# PJ24.net
KiCad netlist of a schematic drawn in EAGLE
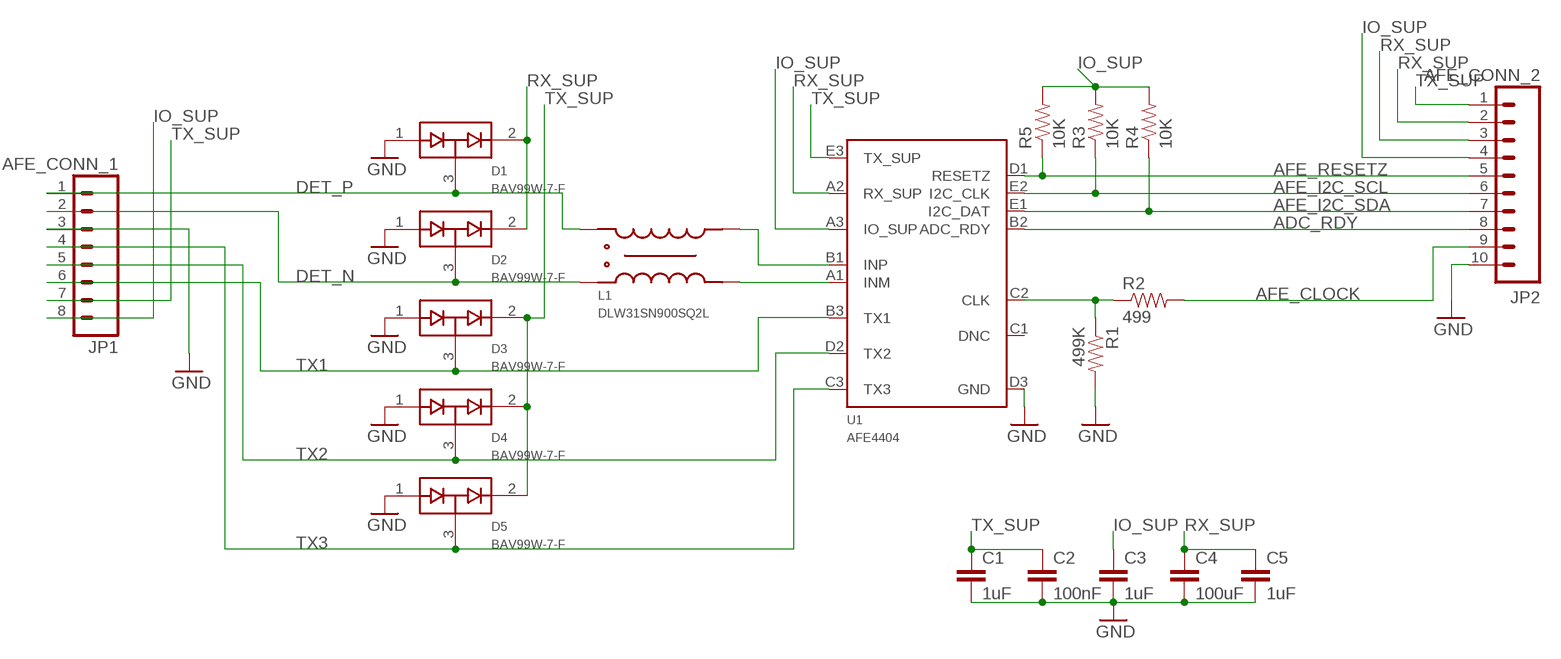
[diagram p0: schematic, sheet 1]
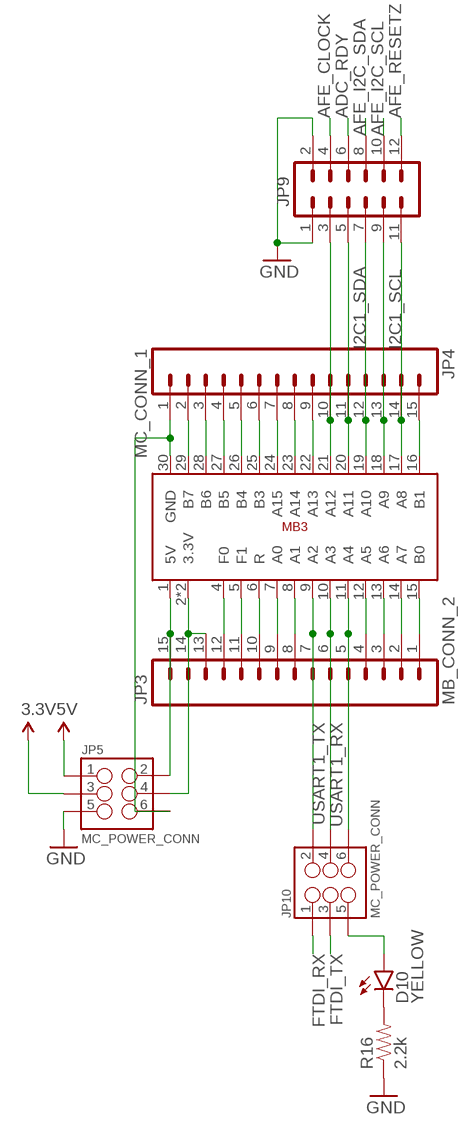
[diagram p1: schematic, sheet 2]
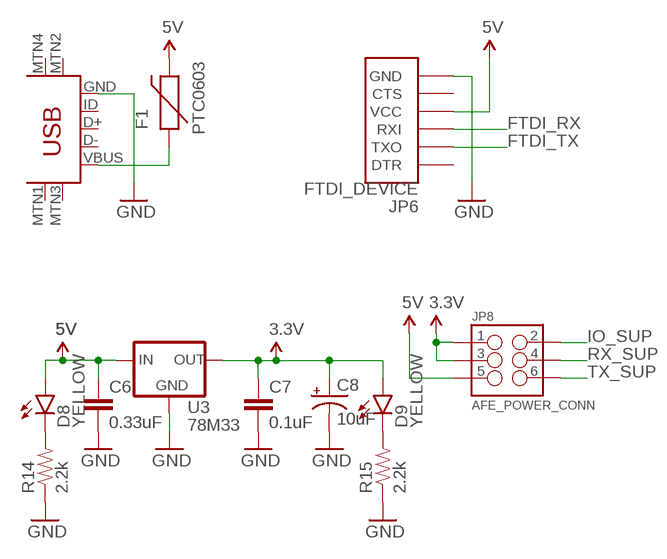
[diagram p2: schematic, sheet 3]
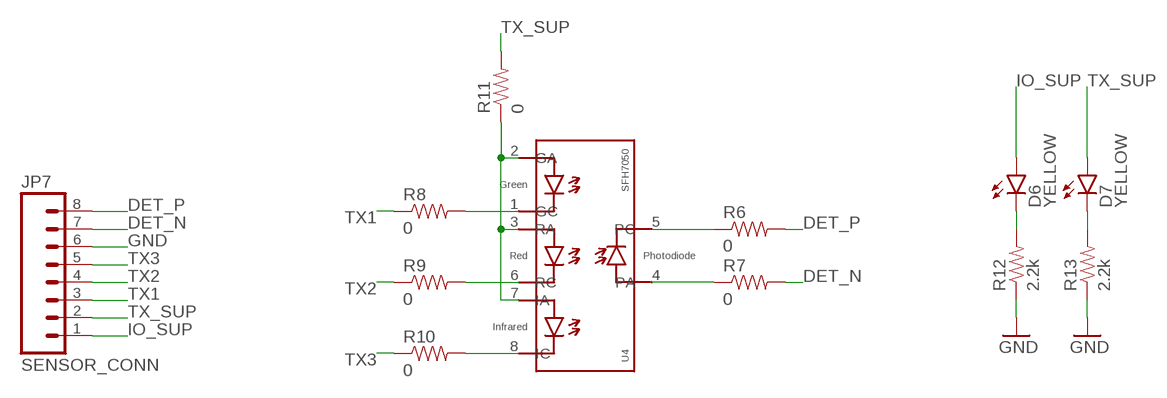
[diagram p3: schematic, sheet 4]

(export (version "E")
  (design (tool "Eeschema 10.0.6"))
  (components
    (comp (ref "D6")
      (value "YELLOW")
      (footprint "eagle-import:LED-1206")
      (libsource (lib "eagle-import") (part "LED-YELLOW1206"))
    )
    (comp (ref "D7")
      (value "YELLOW")
      (footprint "eagle-import:LED-1206")
      (libsource (lib "eagle-import") (part "LED-YELLOW1206"))
    )
    (comp (ref "JP7")
      (value "SENSOR_CONN")
      (footprint "eagle-import:BM08B-SRSS-TB")
      (libsource (lib "eagle-import") (part "M08BM08B-SRSS-TB"))
    )
    (comp (ref "R6")
      (value "0")
      (footprint "eagle-import:0402-S")
      (libsource (lib "eagle-import") (part "RESISTOR0402-S"))
    )
    (comp (ref "R7")
      (value "0")
      (footprint "eagle-import:0402-S")
      (libsource (lib "eagle-import") (part "RESISTOR0402-S"))
    )
    (comp (ref "R8")
      (value "0")
      (footprint "eagle-import:0402-S")
      (libsource (lib "eagle-import") (part "RESISTOR0402-S"))
    )
    (comp (ref "R9")
      (value "0")
      (footprint "eagle-import:0402-S")
      (libsource (lib "eagle-import") (part "RESISTOR0402-S"))
    )
    (comp (ref "R10")
      (value "0")
      (footprint "eagle-import:0402-S")
      (libsource (lib "eagle-import") (part "RESISTOR0402-S"))
    )
    (comp (ref "R11")
      (value "0")
      (footprint "eagle-import:0402-S")
      (libsource (lib "eagle-import") (part "RESISTOR0402-S"))
    )
    (comp (ref "R12")
      (value "2.2k")
      (footprint "eagle-import:0603-RES")
      (libsource (lib "eagle-import") (part "2.2KOHM-1/10W-1%(0603)"))
    )
    (comp (ref "R13")
      (value "2.2k")
      (footprint "eagle-import:0603-RES")
      (libsource (lib "eagle-import") (part "2.2KOHM-1/10W-1%(0603)"))
    )
    (comp (ref "U4")
      (value "SFH7050")
      (footprint "eagle-import:SFH7050")
      (libsource (lib "eagle-import") (part "SFH7050"))
    )
    (comp (ref "C1")
      (value "1uF")
      (footprint "eagle-import:0402-S")
      (libsource (lib "eagle-import") (part "CAP0402-S"))
    )
    (comp (ref "C2")
      (value "100nF")
      (footprint "eagle-import:0402-S")
      (libsource (lib "eagle-import") (part "CAP0402-S"))
    )
    (comp (ref "C3")
      (value "1uF")
      (footprint "eagle-import:0402-S")
      (libsource (lib "eagle-import") (part "CAP0402-S"))
    )
    (comp (ref "C4")
      (value "100uF")
      (footprint "eagle-import:0402-S")
      (libsource (lib "eagle-import") (part "CAP0402-S"))
    )
    (comp (ref "C5")
      (value "1uF")
      (footprint "eagle-import:0402-S")
      (libsource (lib "eagle-import") (part "CAP0402-S"))
    )
    (comp (ref "D1")
      (value "BAV99W-7-F")
      (footprint "eagle-import:SOT323")
      (libsource (lib "eagle-import") (part "BAV99W"))
    )
    (comp (ref "D2")
      (value "BAV99W-7-F")
      (footprint "eagle-import:SOT323")
      (libsource (lib "eagle-import") (part "BAV99W"))
    )
    (comp (ref "D3")
      (value "BAV99W-7-F")
      (footprint "eagle-import:SOT323")
      (libsource (lib "eagle-import") (part "BAV99W"))
    )
    (comp (ref "D4")
      (value "BAV99W-7-F")
      (footprint "eagle-import:SOT323")
      (libsource (lib "eagle-import") (part "BAV99W"))
    )
    (comp (ref "D5")
      (value "BAV99W-7-F")
      (footprint "eagle-import:SOT323")
      (libsource (lib "eagle-import") (part "BAV99W"))
    )
    (comp (ref "JP1")
      (value "AFE_CONN_1")
      (footprint "eagle-import:BM08B-SRSS-TB")
      (libsource (lib "eagle-import") (part "M08BM08B-SRSS-TB"))
    )
    (comp (ref "JP2")
      (value "AFE_CONN_2")
      (footprint "eagle-import:1X10_SMD_MALE")
      (libsource (lib "eagle-import") (part "M10SMD_MALE"))
    )
    (comp (ref "L1")
      (value "DLW31SN900SQ2L")
      (footprint "eagle-import:DLW31SN900SQ2L")
      (libsource (lib "eagle-import") (part "DLW31SN900SQ2L"))
    )
    (comp (ref "R1")
      (value "499K")
      (footprint "eagle-import:0402-S")
      (libsource (lib "eagle-import") (part "RESISTOR0402-S"))
    )
    (comp (ref "R2")
      (value "499")
      (footprint "eagle-import:0402-S")
      (libsource (lib "eagle-import") (part "RESISTOR0402-S"))
    )
    (comp (ref "R3")
      (value "10K")
      (footprint "eagle-import:0402-S")
      (libsource (lib "eagle-import") (part "RESISTOR0402-S"))
    )
    (comp (ref "R4")
      (value "10K")
      (footprint "eagle-import:0402-S")
      (libsource (lib "eagle-import") (part "RESISTOR0402-S"))
    )
    (comp (ref "R5")
      (value "10K")
      (footprint "eagle-import:0402-S")
      (libsource (lib "eagle-import") (part "RESISTOR0402-S"))
    )
    (comp (ref "U1")
      (value "AFE4404")
      (footprint "eagle-import:DSBGA-3X5")
      (libsource (lib "eagle-import") (part "AFE4404"))
    )
    (comp (ref "C6")
      (value "0.33uF")
      (footprint "eagle-import:0805-CAP")
      (libsource (lib "eagle-import") (part "0.33UF-50V-10%(0805)"))
    )
    (comp (ref "C7")
      (value "0.1uF")
      (footprint "eagle-import:0805-CAP")
      (libsource (lib "eagle-import") (part "0.33UF-50V-10%(0805)"))
    )
    (comp (ref "C8")
      (value "10uF")
      (footprint "eagle-import:EIA3216")
      (libsource (lib "eagle-import") (part "10UF-16V-10%(TANT)"))
    )
    (comp (ref "D8")
      (value "YELLOW")
      (footprint "eagle-import:LED-1206")
      (libsource (lib "eagle-import") (part "LED-YELLOW1206"))
    )
    (comp (ref "D9")
      (value "YELLOW")
      (footprint "eagle-import:LED-1206")
      (libsource (lib "eagle-import") (part "LED-YELLOW1206"))
    )
    (comp (ref "F1")
      (value "PTC0603")
      (footprint "eagle-import:0603")
      (libsource (lib "eagle-import") (part "PTC0603"))
    )
    (comp (ref "JP6")
      (value "FTDI_DEVICE")
      (footprint "eagle-import:FTDI_DEVICE_SIDE")
      (libsource (lib "eagle-import") (part "FTDI_DEVICE"))
    )
    (comp (ref "JP8")
      (value "AFE_POWER_CONN")
      (footprint "eagle-import:2X3_SMT_POSTS")
      (libsource (lib "eagle-import") (part "M03X2SMT"))
    )
    (comp (ref "R14")
      (value "2.2k")
      (footprint "eagle-import:0603-RES")
      (libsource (lib "eagle-import") (part "2.2KOHM-1/10W-1%(0603)"))
    )
    (comp (ref "R15")
      (value "2.2k")
      (footprint "eagle-import:0603-RES")
      (libsource (lib "eagle-import") (part "2.2KOHM-1/10W-1%(0603)"))
    )
    (comp (ref "U$1")
      (value "USB-MINIB-5PIN")
      (footprint "eagle-import:USB-MINIB")
      (libsource (lib "eagle-import") (part "USB-MINIB-5PIN"))
    )
    (comp (ref "U3")
      (value "78M33")
      (footprint "eagle-import:TO-252")
      (libsource (lib "eagle-import") (part "V_REG_78XX7812"))
    )
    (comp (ref "D10")
      (value "YELLOW")
      (footprint "eagle-import:LED-1206")
      (libsource (lib "eagle-import") (part "LED-YELLOW1206"))
    )
    (comp (ref "JP3")
      (value "MB_CONN_2")
      (footprint "eagle-import:1X15_LOCK")
      (libsource (lib "eagle-import") (part "M15LOCK"))
    )
    (comp (ref "JP4")
      (value "MC_CONN_1")
      (footprint "eagle-import:1X15_LOCK")
      (libsource (lib "eagle-import") (part "M15LOCK"))
    )
    (comp (ref "JP5")
      (value "MC_POWER_CONN")
      (footprint "eagle-import:2X3_SMT_POSTS")
      (libsource (lib "eagle-import") (part "M03X2SMT"))
    )
    (comp (ref "JP9")
      (value "M06X2FEMALE-SMT")
      (footprint "eagle-import:2X6_SMD")
      (libsource (lib "eagle-import") (part "M06X2FEMALE-SMT"))
    )
    (comp (ref "JP10")
      (value "MC_POWER_CONN")
      (footprint "eagle-import:2X3_SMT_POSTS")
      (libsource (lib "eagle-import") (part "M03X2SMT"))
    )
    (comp (ref "R16")
      (value "2.2k")
      (footprint "eagle-import:0603-RES")
      (libsource (lib "eagle-import") (part "2.2KOHM-1/10W-1%(0603)"))
    )
    (comp (ref "U2")
      (value "MB3")
      (footprint "eagle-import:MB3")
      (libsource (lib "eagle-import") (part "MB3"))
    )
  )
  (nets
    (net (code "1") (name "3.3V") (class "Default")
      (node (ref "C7") (pin "1") (pinfunction "1_1") (pintype "passive"))
      (node (ref "C8") (pin "A") (pinfunction "+_A") (pintype "passive"))
      (node (ref "D9") (pin "A") (pinfunction "A_A") (pintype "passive"))
      (node (ref "JP5") (pin "3") (pinfunction "3_3") (pintype "bidirectional"))
      (node (ref "JP8") (pin "1") (pinfunction "1_1") (pintype "bidirectional"))
      (node (ref "JP8") (pin "3") (pinfunction "3_3") (pintype "bidirectional"))
      (node (ref "U3") (pin "2") (pinfunction "OUT_2") (pintype "passive"))
    )
    (net (code "2") (name "5V") (class "Default")
      (node (ref "C6") (pin "1") (pinfunction "1_1") (pintype "passive"))
      (node (ref "D8") (pin "A") (pinfunction "A_A") (pintype "passive"))
      (node (ref "F1") (pin "2") (pinfunction "2_2") (pintype "bidirectional"))
      (node (ref "JP5") (pin "1") (pinfunction "1_1") (pintype "bidirectional"))
      (node (ref "JP6") (pin "P$4") (pinfunction "VCC_P$4") (pintype "bidirectional"))
      (node (ref "JP8") (pin "5") (pinfunction "5_5") (pintype "bidirectional"))
      (node (ref "U3") (pin "1") (pinfunction "IN_1") (pintype "input"))
    )
    (net (code "3") (name "ADC_RDY") (class "Default")
      (node (ref "JP2") (pin "8") (pinfunction "8_8") (pintype "passive"))
      (node (ref "JP9") (pin "6") (pinfunction "6_6") (pintype "passive"))
      (node (ref "U1") (pin "B2") (pinfunction "ADC_RDY_B2") (pintype "bidirectional"))
    )
    (net (code "4") (name "AFE_CLOCK") (class "Default")
      (node (ref "JP2") (pin "9") (pinfunction "9_9") (pintype "passive"))
      (node (ref "JP9") (pin "4") (pinfunction "4_4") (pintype "passive"))
      (node (ref "R2") (pin "2") (pinfunction "2_2") (pintype "passive"))
    )
    (net (code "5") (name "AFE_I2C_SCL") (class "Default")
      (node (ref "JP2") (pin "6") (pinfunction "6_6") (pintype "passive"))
      (node (ref "JP9") (pin "10") (pinfunction "10_10") (pintype "passive"))
      (node (ref "R3") (pin "1") (pinfunction "1_1") (pintype "passive"))
      (node (ref "U1") (pin "E2") (pinfunction "I2C_CLK_E2") (pintype "bidirectional"))
    )
    (net (code "6") (name "AFE_I2C_SDA") (class "Default")
      (node (ref "JP2") (pin "7") (pinfunction "7_7") (pintype "passive"))
      (node (ref "JP9") (pin "8") (pinfunction "8_8") (pintype "passive"))
      (node (ref "R4") (pin "1") (pinfunction "1_1") (pintype "passive"))
      (node (ref "U1") (pin "E1") (pinfunction "I2C_DAT_E1") (pintype "bidirectional"))
    )
    (net (code "7") (name "AFE_RESETZ") (class "Default")
      (node (ref "JP2") (pin "5") (pinfunction "5_5") (pintype "passive"))
      (node (ref "JP9") (pin "12") (pinfunction "12_12") (pintype "passive"))
      (node (ref "R5") (pin "1") (pinfunction "1_1") (pintype "passive"))
      (node (ref "U1") (pin "D1") (pinfunction "RESETZ_D1") (pintype "bidirectional"))
    )
    (net (code "8") (name "DET_N") (class "Default")
      (node (ref "D2") (pin "3") (pinfunction "COM_3") (pintype "bidirectional"))
      (node (ref "JP1") (pin "2") (pinfunction "2_2") (pintype "passive"))
      (node (ref "JP7") (pin "7") (pinfunction "7_7") (pintype "passive"))
      (node (ref "L1") (pin "4") (pinfunction "4_4") (pintype "bidirectional"))
      (node (ref "R7") (pin "2") (pinfunction "2_2") (pintype "passive"))
    )
    (net (code "9") (name "DET_P") (class "Default")
      (node (ref "D1") (pin "3") (pinfunction "COM_3") (pintype "bidirectional"))
      (node (ref "JP1") (pin "1") (pinfunction "1_1") (pintype "passive"))
      (node (ref "JP7") (pin "8") (pinfunction "8_8") (pintype "passive"))
      (node (ref "L1") (pin "1") (pinfunction "1_1") (pintype "bidirectional"))
      (node (ref "R6") (pin "2") (pinfunction "2_2") (pintype "passive"))
    )
    (net (code "10") (name "FTDI_RX") (class "Default")
      (node (ref "JP10") (pin "1") (pinfunction "1_1") (pintype "bidirectional"))
      (node (ref "JP6") (pin "P$3") (pinfunction "RXI_P$3") (pintype "bidirectional"))
    )
    (net (code "11") (name "FTDI_TX") (class "Default")
      (node (ref "JP10") (pin "3") (pinfunction "3_3") (pintype "bidirectional"))
      (node (ref "JP6") (pin "P$2") (pinfunction "TXO_P$2") (pintype "bidirectional"))
    )
    (net (code "12") (name "GND") (class "Default")
      (node (ref "C1") (pin "2") (pinfunction "2_2") (pintype "passive"))
      (node (ref "C2") (pin "2") (pinfunction "2_2") (pintype "passive"))
      (node (ref "C3") (pin "2") (pinfunction "2_2") (pintype "passive"))
      (node (ref "C4") (pin "2") (pinfunction "2_2") (pintype "passive"))
      (node (ref "C5") (pin "2") (pinfunction "2_2") (pintype "passive"))
      (node (ref "C6") (pin "2") (pinfunction "2_2") (pintype "passive"))
      (node (ref "C7") (pin "2") (pinfunction "2_2") (pintype "passive"))
      (node (ref "C8") (pin "C") (pinfunction "-_C") (pintype "passive"))
      (node (ref "D1") (pin "1") (pinfunction "A1_1") (pintype "bidirectional"))
      (node (ref "D2") (pin "1") (pinfunction "A1_1") (pintype "bidirectional"))
      (node (ref "D3") (pin "1") (pinfunction "A1_1") (pintype "bidirectional"))
      (node (ref "D4") (pin "1") (pinfunction "A1_1") (pintype "bidirectional"))
      (node (ref "D5") (pin "1") (pinfunction "A1_1") (pintype "bidirectional"))
      (node (ref "JP1") (pin "3") (pinfunction "3_3") (pintype "passive"))
      (node (ref "JP2") (pin "10") (pinfunction "10_10") (pintype "passive"))
      (node (ref "JP5") (pin "5") (pinfunction "5_5") (pintype "bidirectional"))
      (node (ref "JP6") (pin "P$6") (pinfunction "GND_P$6") (pintype "bidirectional"))
      (node (ref "JP7") (pin "6") (pinfunction "6_6") (pintype "passive"))
      (node (ref "JP9") (pin "1") (pinfunction "1_1") (pintype "passive"))
      (node (ref "JP9") (pin "2") (pinfunction "2_2") (pintype "passive"))
      (node (ref "R1") (pin "2") (pinfunction "2_2") (pintype "passive"))
      (node (ref "R12") (pin "1") (pinfunction "1_1") (pintype "passive"))
      (node (ref "R13") (pin "1") (pinfunction "1_1") (pintype "passive"))
      (node (ref "R14") (pin "1") (pinfunction "1_1") (pintype "passive"))
      (node (ref "R15") (pin "1") (pinfunction "1_1") (pintype "passive"))
      (node (ref "R16") (pin "1") (pinfunction "1_1") (pintype "passive"))
      (node (ref "U$1") (pin "GND") (pinfunction "GND_GND") (pintype "bidirectional"))
      (node (ref "U1") (pin "D3") (pinfunction "GND_D3") (pintype "bidirectional"))
      (node (ref "U3") (pin "3") (pinfunction "GND_3") (pintype "input"))
    )
    (net (code "13") (name "I2C1_SCL") (class "Default")
      (node (ref "JP4") (pin "13") (pinfunction "13_13") (pintype "passive"))
      (node (ref "JP9") (pin "9") (pinfunction "9_9") (pintype "passive"))
      (node (ref "U2") (pin "18") (pinfunction "A9_18") (pintype "bidirectional"))
    )
    (net (code "14") (name "I2C1_SDA") (class "Default")
      (node (ref "JP4") (pin "12") (pinfunction "12_12") (pintype "passive"))
      (node (ref "JP9") (pin "7") (pinfunction "7_7") (pintype "passive"))
      (node (ref "U2") (pin "19") (pinfunction "A10_19") (pintype "bidirectional"))
    )
    (net (code "15") (name "IO_SUP") (class "Default")
      (node (ref "C3") (pin "1") (pinfunction "1_1") (pintype "passive"))
      (node (ref "D6") (pin "A") (pinfunction "A_A") (pintype "passive"))
      (node (ref "JP1") (pin "8") (pinfunction "8_8") (pintype "passive"))
      (node (ref "JP2") (pin "4") (pinfunction "4_4") (pintype "passive"))
      (node (ref "JP7") (pin "1") (pinfunction "1_1") (pintype "passive"))
      (node (ref "JP8") (pin "2") (pinfunction "2_2") (pintype "bidirectional"))
      (node (ref "R3") (pin "2") (pinfunction "2_2") (pintype "passive"))
      (node (ref "R4") (pin "2") (pinfunction "2_2") (pintype "passive"))
      (node (ref "R5") (pin "2") (pinfunction "2_2") (pintype "passive"))
      (node (ref "U1") (pin "A3") (pinfunction "IO_SUP_A3") (pintype "bidirectional"))
    )
    (net (code "16") (name "Net-(D6-PadC)") (class "Default")
      (node (ref "D6") (pin "C") (pinfunction "C_C") (pintype "passive"))
      (node (ref "R12") (pin "2") (pinfunction "2_2") (pintype "passive"))
    )
    (net (code "17") (name "Net-(D7-PadC)") (class "Default")
      (node (ref "D7") (pin "C") (pinfunction "C_C") (pintype "passive"))
      (node (ref "R13") (pin "2") (pinfunction "2_2") (pintype "passive"))
    )
    (net (code "18") (name "Net-(D8-PadC)") (class "Default")
      (node (ref "D8") (pin "C") (pinfunction "C_C") (pintype "passive"))
      (node (ref "R14") (pin "2") (pinfunction "2_2") (pintype "passive"))
    )
    (net (code "19") (name "Net-(D9-PadC)") (class "Default")
      (node (ref "D9") (pin "C") (pinfunction "C_C") (pintype "passive"))
      (node (ref "R15") (pin "2") (pinfunction "2_2") (pintype "passive"))
    )
    (net (code "20") (name "Net-(D10-PadA)") (class "Default")
      (node (ref "D10") (pin "A") (pinfunction "A_A") (pintype "passive"))
      (node (ref "JP10") (pin "5") (pinfunction "5_5") (pintype "bidirectional"))
    )
    (net (code "21") (name "Net-(D10-PadC)") (class "Default")
      (node (ref "D10") (pin "C") (pinfunction "C_C") (pintype "passive"))
      (node (ref "R16") (pin "2") (pinfunction "2_2") (pintype "passive"))
    )
    (net (code "22") (name "Net-(F1-Pad1)") (class "Default")
      (node (ref "F1") (pin "1") (pinfunction "1_1") (pintype "bidirectional"))
      (node (ref "U$1") (pin "VBUS") (pinfunction "VBUS_VBUS") (pintype "bidirectional"))
    )
    (net (code "23") (name "Net-(JP3-Pad13)") (class "Default")
      (node (ref "JP3") (pin "13") (pinfunction "13_13") (pintype "passive"))
      (node (ref "JP3") (pin "14") (pinfunction "14_14") (pintype "passive"))
      (node (ref "JP5") (pin "4") (pinfunction "4_4") (pintype "bidirectional"))
      (node (ref "U2") (pin "2") (pinfunction "3.3V_2") (pintype "bidirectional"))
      (node (ref "U2") (pin "3") (pinfunction "3.3V_3") (pintype "bidirectional"))
    )
    (net (code "24") (name "Net-(U1-CLK)") (class "Default")
      (node (ref "R1") (pin "1") (pinfunction "1_1") (pintype "passive"))
      (node (ref "R2") (pin "1") (pinfunction "1_1") (pintype "passive"))
      (node (ref "U1") (pin "C2") (pinfunction "CLK_C2") (pintype "bidirectional"))
    )
    (net (code "25") (name "Net-(U1-INM)") (class "Default")
      (node (ref "L1") (pin "3") (pinfunction "3_3") (pintype "bidirectional"))
      (node (ref "U1") (pin "A1") (pinfunction "INM_A1") (pintype "bidirectional"))
    )
    (net (code "26") (name "Net-(U1-INP)") (class "Default")
      (node (ref "L1") (pin "2") (pinfunction "2_2") (pintype "bidirectional"))
      (node (ref "U1") (pin "B1") (pinfunction "INP_B1") (pintype "bidirectional"))
    )
    (net (code "27") (name "Net-(U2-5V)") (class "Default")
      (node (ref "JP3") (pin "15") (pinfunction "15_15") (pintype "passive"))
      (node (ref "JP5") (pin "2") (pinfunction "2_2") (pintype "bidirectional"))
      (node (ref "U2") (pin "1") (pinfunction "5V_1") (pintype "bidirectional"))
    )
    (net (code "28") (name "Net-(U2-A0)") (class "Default")
      (node (ref "JP3") (pin "9") (pinfunction "9_9") (pintype "passive"))
      (node (ref "U2") (pin "7") (pinfunction "A0_7") (pintype "bidirectional"))
    )
    (net (code "29") (name "Net-(U2-A1)") (class "Default")
      (node (ref "JP3") (pin "8") (pinfunction "8_8") (pintype "passive"))
      (node (ref "U2") (pin "8") (pinfunction "A1_8") (pintype "bidirectional"))
    )
    (net (code "30") (name "Net-(U2-A4)") (class "Default")
      (node (ref "JP10") (pin "6") (pinfunction "6_6") (pintype "bidirectional"))
      (node (ref "JP3") (pin "5") (pinfunction "5_5") (pintype "passive"))
      (node (ref "U2") (pin "11") (pinfunction "A4_11") (pintype "bidirectional"))
    )
    (net (code "31") (name "Net-(U2-A5)") (class "Default")
      (node (ref "JP3") (pin "4") (pinfunction "4_4") (pintype "passive"))
      (node (ref "U2") (pin "12") (pinfunction "A5_12") (pintype "bidirectional"))
    )
    (net (code "32") (name "Net-(U2-A6)") (class "Default")
      (node (ref "JP3") (pin "3") (pinfunction "3_3") (pintype "passive"))
      (node (ref "U2") (pin "13") (pinfunction "A6_13") (pintype "bidirectional"))
    )
    (net (code "33") (name "Net-(U2-A7)") (class "Default")
      (node (ref "JP3") (pin "2") (pinfunction "2_2") (pintype "passive"))
      (node (ref "U2") (pin "14") (pinfunction "A7_14") (pintype "bidirectional"))
    )
    (net (code "34") (name "Net-(U2-A8)") (class "Default")
      (node (ref "JP4") (pin "14") (pinfunction "14_14") (pintype "passive"))
      (node (ref "JP9") (pin "11") (pinfunction "11_11") (pintype "passive"))
      (node (ref "U2") (pin "17") (pinfunction "A8_17") (pintype "bidirectional"))
    )
    (net (code "35") (name "Net-(U2-A11)") (class "Default")
      (node (ref "JP4") (pin "11") (pinfunction "11_11") (pintype "passive"))
      (node (ref "JP9") (pin "5") (pinfunction "5_5") (pintype "passive"))
      (node (ref "U2") (pin "20") (pinfunction "A11_20") (pintype "bidirectional"))
    )
    (net (code "36") (name "Net-(U2-A12)") (class "Default")
      (node (ref "JP4") (pin "10") (pinfunction "10_10") (pintype "passive"))
      (node (ref "JP9") (pin "3") (pinfunction "3_3") (pintype "passive"))
      (node (ref "U2") (pin "21") (pinfunction "A12_21") (pintype "bidirectional"))
    )
    (net (code "37") (name "Net-(U2-A13)") (class "Default")
      (node (ref "JP4") (pin "9") (pinfunction "9_9") (pintype "passive"))
      (node (ref "U2") (pin "22") (pinfunction "A13_22") (pintype "bidirectional"))
    )
    (net (code "38") (name "Net-(U2-A14)") (class "Default")
      (node (ref "JP4") (pin "8") (pinfunction "8_8") (pintype "passive"))
      (node (ref "U2") (pin "23") (pinfunction "A14_23") (pintype "bidirectional"))
    )
    (net (code "39") (name "Net-(U2-A15)") (class "Default")
      (node (ref "JP4") (pin "7") (pinfunction "7_7") (pintype "passive"))
      (node (ref "U2") (pin "24") (pinfunction "A15_24") (pintype "bidirectional"))
    )
    (net (code "40") (name "Net-(U2-B0)") (class "Default")
      (node (ref "JP3") (pin "1") (pinfunction "1_1") (pintype "passive"))
      (node (ref "U2") (pin "15") (pinfunction "B0_15") (pintype "bidirectional"))
    )
    (net (code "41") (name "Net-(U2-B1)") (class "Default")
      (node (ref "JP4") (pin "15") (pinfunction "15_15") (pintype "passive"))
      (node (ref "U2") (pin "16") (pinfunction "B1_16") (pintype "bidirectional"))
    )
    (net (code "42") (name "Net-(U2-B3)") (class "Default")
      (node (ref "JP4") (pin "6") (pinfunction "6_6") (pintype "passive"))
      (node (ref "U2") (pin "25") (pinfunction "B3_25") (pintype "bidirectional"))
    )
    (net (code "43") (name "Net-(U2-B4)") (class "Default")
      (node (ref "JP4") (pin "5") (pinfunction "5_5") (pintype "passive"))
      (node (ref "U2") (pin "26") (pinfunction "B4_26") (pintype "bidirectional"))
    )
    (net (code "44") (name "Net-(U2-B5)") (class "Default")
      (node (ref "JP4") (pin "4") (pinfunction "4_4") (pintype "passive"))
      (node (ref "U2") (pin "27") (pinfunction "B5_27") (pintype "bidirectional"))
    )
    (net (code "45") (name "Net-(U2-B6)") (class "Default")
      (node (ref "JP4") (pin "3") (pinfunction "3_3") (pintype "passive"))
      (node (ref "U2") (pin "28") (pinfunction "B6_28") (pintype "bidirectional"))
    )
    (net (code "46") (name "Net-(U2-B7)") (class "Default")
      (node (ref "JP4") (pin "2") (pinfunction "2_2") (pintype "passive"))
      (node (ref "U2") (pin "29") (pinfunction "B7_29") (pintype "bidirectional"))
    )
    (net (code "47") (name "Net-(U2-F0)") (class "Default")
      (node (ref "JP3") (pin "12") (pinfunction "12_12") (pintype "passive"))
      (node (ref "U2") (pin "4") (pinfunction "F0_4") (pintype "bidirectional"))
    )
    (net (code "48") (name "Net-(U2-F1)") (class "Default")
      (node (ref "JP3") (pin "11") (pinfunction "11_11") (pintype "passive"))
      (node (ref "U2") (pin "5") (pinfunction "F1_5") (pintype "bidirectional"))
    )
    (net (code "49") (name "Net-(U2-GND)") (class "Default")
      (node (ref "JP4") (pin "1") (pinfunction "1_1") (pintype "passive"))
      (node (ref "JP5") (pin "6") (pinfunction "6_6") (pintype "bidirectional"))
      (node (ref "U2") (pin "30") (pinfunction "GND_30") (pintype "bidirectional"))
    )
    (net (code "50") (name "Net-(U2-R)") (class "Default")
      (node (ref "JP3") (pin "10") (pinfunction "10_10") (pintype "passive"))
      (node (ref "U2") (pin "6") (pinfunction "R_6") (pintype "bidirectional"))
    )
    (net (code "51") (name "Net-(U4-GA)") (class "Default")
      (node (ref "R11") (pin "1") (pinfunction "1_1") (pintype "passive"))
      (node (ref "U4") (pin "2") (pinfunction "GA_2") (pintype "bidirectional"))
      (node (ref "U4") (pin "3") (pinfunction "RA_3") (pintype "bidirectional"))
      (node (ref "U4") (pin "7") (pinfunction "IA_7") (pintype "bidirectional"))
    )
    (net (code "52") (name "Net-(U4-GC)") (class "Default")
      (node (ref "R8") (pin "2") (pinfunction "2_2") (pintype "passive"))
      (node (ref "U4") (pin "1") (pinfunction "GC_1") (pintype "bidirectional"))
    )
    (net (code "53") (name "Net-(U4-IC)") (class "Default")
      (node (ref "R10") (pin "2") (pinfunction "2_2") (pintype "passive"))
      (node (ref "U4") (pin "8") (pinfunction "IC_8") (pintype "bidirectional"))
    )
    (net (code "54") (name "Net-(U4-PA)") (class "Default")
      (node (ref "R7") (pin "1") (pinfunction "1_1") (pintype "passive"))
      (node (ref "U4") (pin "4") (pinfunction "PA_4") (pintype "bidirectional"))
    )
    (net (code "55") (name "Net-(U4-PC)") (class "Default")
      (node (ref "R6") (pin "1") (pinfunction "1_1") (pintype "passive"))
      (node (ref "U4") (pin "5") (pinfunction "PC_5") (pintype "bidirectional"))
    )
    (net (code "56") (name "Net-(U4-RC)") (class "Default")
      (node (ref "R9") (pin "2") (pinfunction "2_2") (pintype "passive"))
      (node (ref "U4") (pin "6") (pinfunction "RC_6") (pintype "bidirectional"))
    )
    (net (code "57") (name "RX_SUP") (class "Default")
      (node (ref "C4") (pin "1") (pinfunction "1_1") (pintype "passive"))
      (node (ref "C5") (pin "1") (pinfunction "1_1") (pintype "passive"))
      (node (ref "D1") (pin "2") (pinfunction "C2_2") (pintype "bidirectional"))
      (node (ref "D2") (pin "2") (pinfunction "C2_2") (pintype "bidirectional"))
      (node (ref "JP2") (pin "2") (pinfunction "2_2") (pintype "passive"))
      (node (ref "JP2") (pin "3") (pinfunction "3_3") (pintype "passive"))
      (node (ref "JP8") (pin "4") (pinfunction "4_4") (pintype "bidirectional"))
      (node (ref "U1") (pin "A2") (pinfunction "RX_SUP_A2") (pintype "bidirectional"))
    )
    (net (code "58") (name "TX1") (class "Default")
      (node (ref "D3") (pin "3") (pinfunction "COM_3") (pintype "bidirectional"))
      (node (ref "JP1") (pin "6") (pinfunction "6_6") (pintype "passive"))
      (node (ref "JP7") (pin "3") (pinfunction "3_3") (pintype "passive"))
      (node (ref "R8") (pin "1") (pinfunction "1_1") (pintype "passive"))
      (node (ref "U1") (pin "B3") (pinfunction "TX1_B3") (pintype "bidirectional"))
    )
    (net (code "59") (name "TX2") (class "Default")
      (node (ref "D4") (pin "3") (pinfunction "COM_3") (pintype "bidirectional"))
      (node (ref "JP1") (pin "5") (pinfunction "5_5") (pintype "passive"))
      (node (ref "JP7") (pin "4") (pinfunction "4_4") (pintype "passive"))
      (node (ref "R9") (pin "1") (pinfunction "1_1") (pintype "passive"))
      (node (ref "U1") (pin "D2") (pinfunction "TX2_D2") (pintype "bidirectional"))
    )
    (net (code "60") (name "TX3") (class "Default")
      (node (ref "D5") (pin "3") (pinfunction "COM_3") (pintype "bidirectional"))
      (node (ref "JP1") (pin "4") (pinfunction "4_4") (pintype "passive"))
      (node (ref "JP7") (pin "5") (pinfunction "5_5") (pintype "passive"))
      (node (ref "R10") (pin "1") (pinfunction "1_1") (pintype "passive"))
      (node (ref "U1") (pin "C3") (pinfunction "TX3_C3") (pintype "bidirectional"))
    )
    (net (code "61") (name "TX_SUP") (class "Default")
      (node (ref "C1") (pin "1") (pinfunction "1_1") (pintype "passive"))
      (node (ref "C2") (pin "1") (pinfunction "1_1") (pintype "passive"))
      (node (ref "D3") (pin "2") (pinfunction "C2_2") (pintype "bidirectional"))
      (node (ref "D4") (pin "2") (pinfunction "C2_2") (pintype "bidirectional"))
      (node (ref "D5") (pin "2") (pinfunction "C2_2") (pintype "bidirectional"))
      (node (ref "D7") (pin "A") (pinfunction "A_A") (pintype "passive"))
      (node (ref "JP1") (pin "7") (pinfunction "7_7") (pintype "passive"))
      (node (ref "JP2") (pin "1") (pinfunction "1_1") (pintype "passive"))
      (node (ref "JP7") (pin "2") (pinfunction "2_2") (pintype "passive"))
      (node (ref "JP8") (pin "6") (pinfunction "6_6") (pintype "bidirectional"))
      (node (ref "R11") (pin "2") (pinfunction "2_2") (pintype "passive"))
      (node (ref "U1") (pin "E3") (pinfunction "TX_SUP_E3") (pintype "bidirectional"))
    )
    (net (code "62") (name "USART1_RX") (class "Default")
      (node (ref "JP10") (pin "4") (pinfunction "4_4") (pintype "bidirectional"))
      (node (ref "JP3") (pin "6") (pinfunction "6_6") (pintype "passive"))
      (node (ref "U2") (pin "10") (pinfunction "A3_10") (pintype "bidirectional"))
    )
    (net (code "63") (name "USART1_TX") (class "Default")
      (node (ref "JP10") (pin "2") (pinfunction "2_2") (pintype "bidirectional"))
      (node (ref "JP3") (pin "7") (pinfunction "7_7") (pintype "passive"))
      (node (ref "U2") (pin "9") (pinfunction "A2_9") (pintype "bidirectional"))
    )
    (net (code "64") (name "unconnected-(JP6-CTS-PadP$5)") (class "Default")
      (node (ref "JP6") (pin "P$5") (pinfunction "CTS_P$5") (pintype "bidirectional"))
    )
    (net (code "65") (name "unconnected-(JP6-DTR-PadP$1)") (class "Default")
      (node (ref "JP6") (pin "P$1") (pinfunction "DTR_P$1") (pintype "bidirectional"))
    )
    (net (code "66") (name "unconnected-(U$1-MTN1-PadMTN3)") (class "Default")
      (node (ref "U$1") (pin "MTN3") (pinfunction "MTN1_MTN3") (pintype "bidirectional"))
    )
    (net (code "67") (name "unconnected-(U$1-MTN2-PadMTN1)") (class "Default")
      (node (ref "U$1") (pin "MTN1") (pinfunction "MTN2_MTN1") (pintype "bidirectional"))
    )
    (net (code "68") (name "unconnected-(U$1-MTN3-PadMTN2)") (class "Default")
      (node (ref "U$1") (pin "MTN2") (pinfunction "MTN3_MTN2") (pintype "bidirectional"))
    )
    (net (code "69") (name "unconnected-(U$1-PadD+)") (class "Default")
      (node (ref "U$1") (pin "D+") (pinfunction "D+_D+") (pintype "bidirectional"))
    )
    (net (code "70") (name "unconnected-(U$1-PadD-)") (class "Default")
      (node (ref "U$1") (pin "D-") (pinfunction "D-_D-") (pintype "bidirectional"))
    )
    (net (code "71") (name "unconnected-(U$1-PadID)") (class "Default")
      (node (ref "U$1") (pin "ID") (pinfunction "ID_ID") (pintype "bidirectional"))
    )
    (net (code "72") (name "unconnected-(U$1-PadMTN4)") (class "Default")
      (node (ref "U$1") (pin "MTN4") (pinfunction "MTN4_MTN4") (pintype "bidirectional"))
    )
    (net (code "73") (name "unconnected-(U1-DNC-PadC1)") (class "Default")
      (node (ref "U1") (pin "C1") (pinfunction "DNC_C1") (pintype "bidirectional"))
    )
  )
)
